# CANoPi.net
KiCad netlist of a schematic drawn in EAGLE
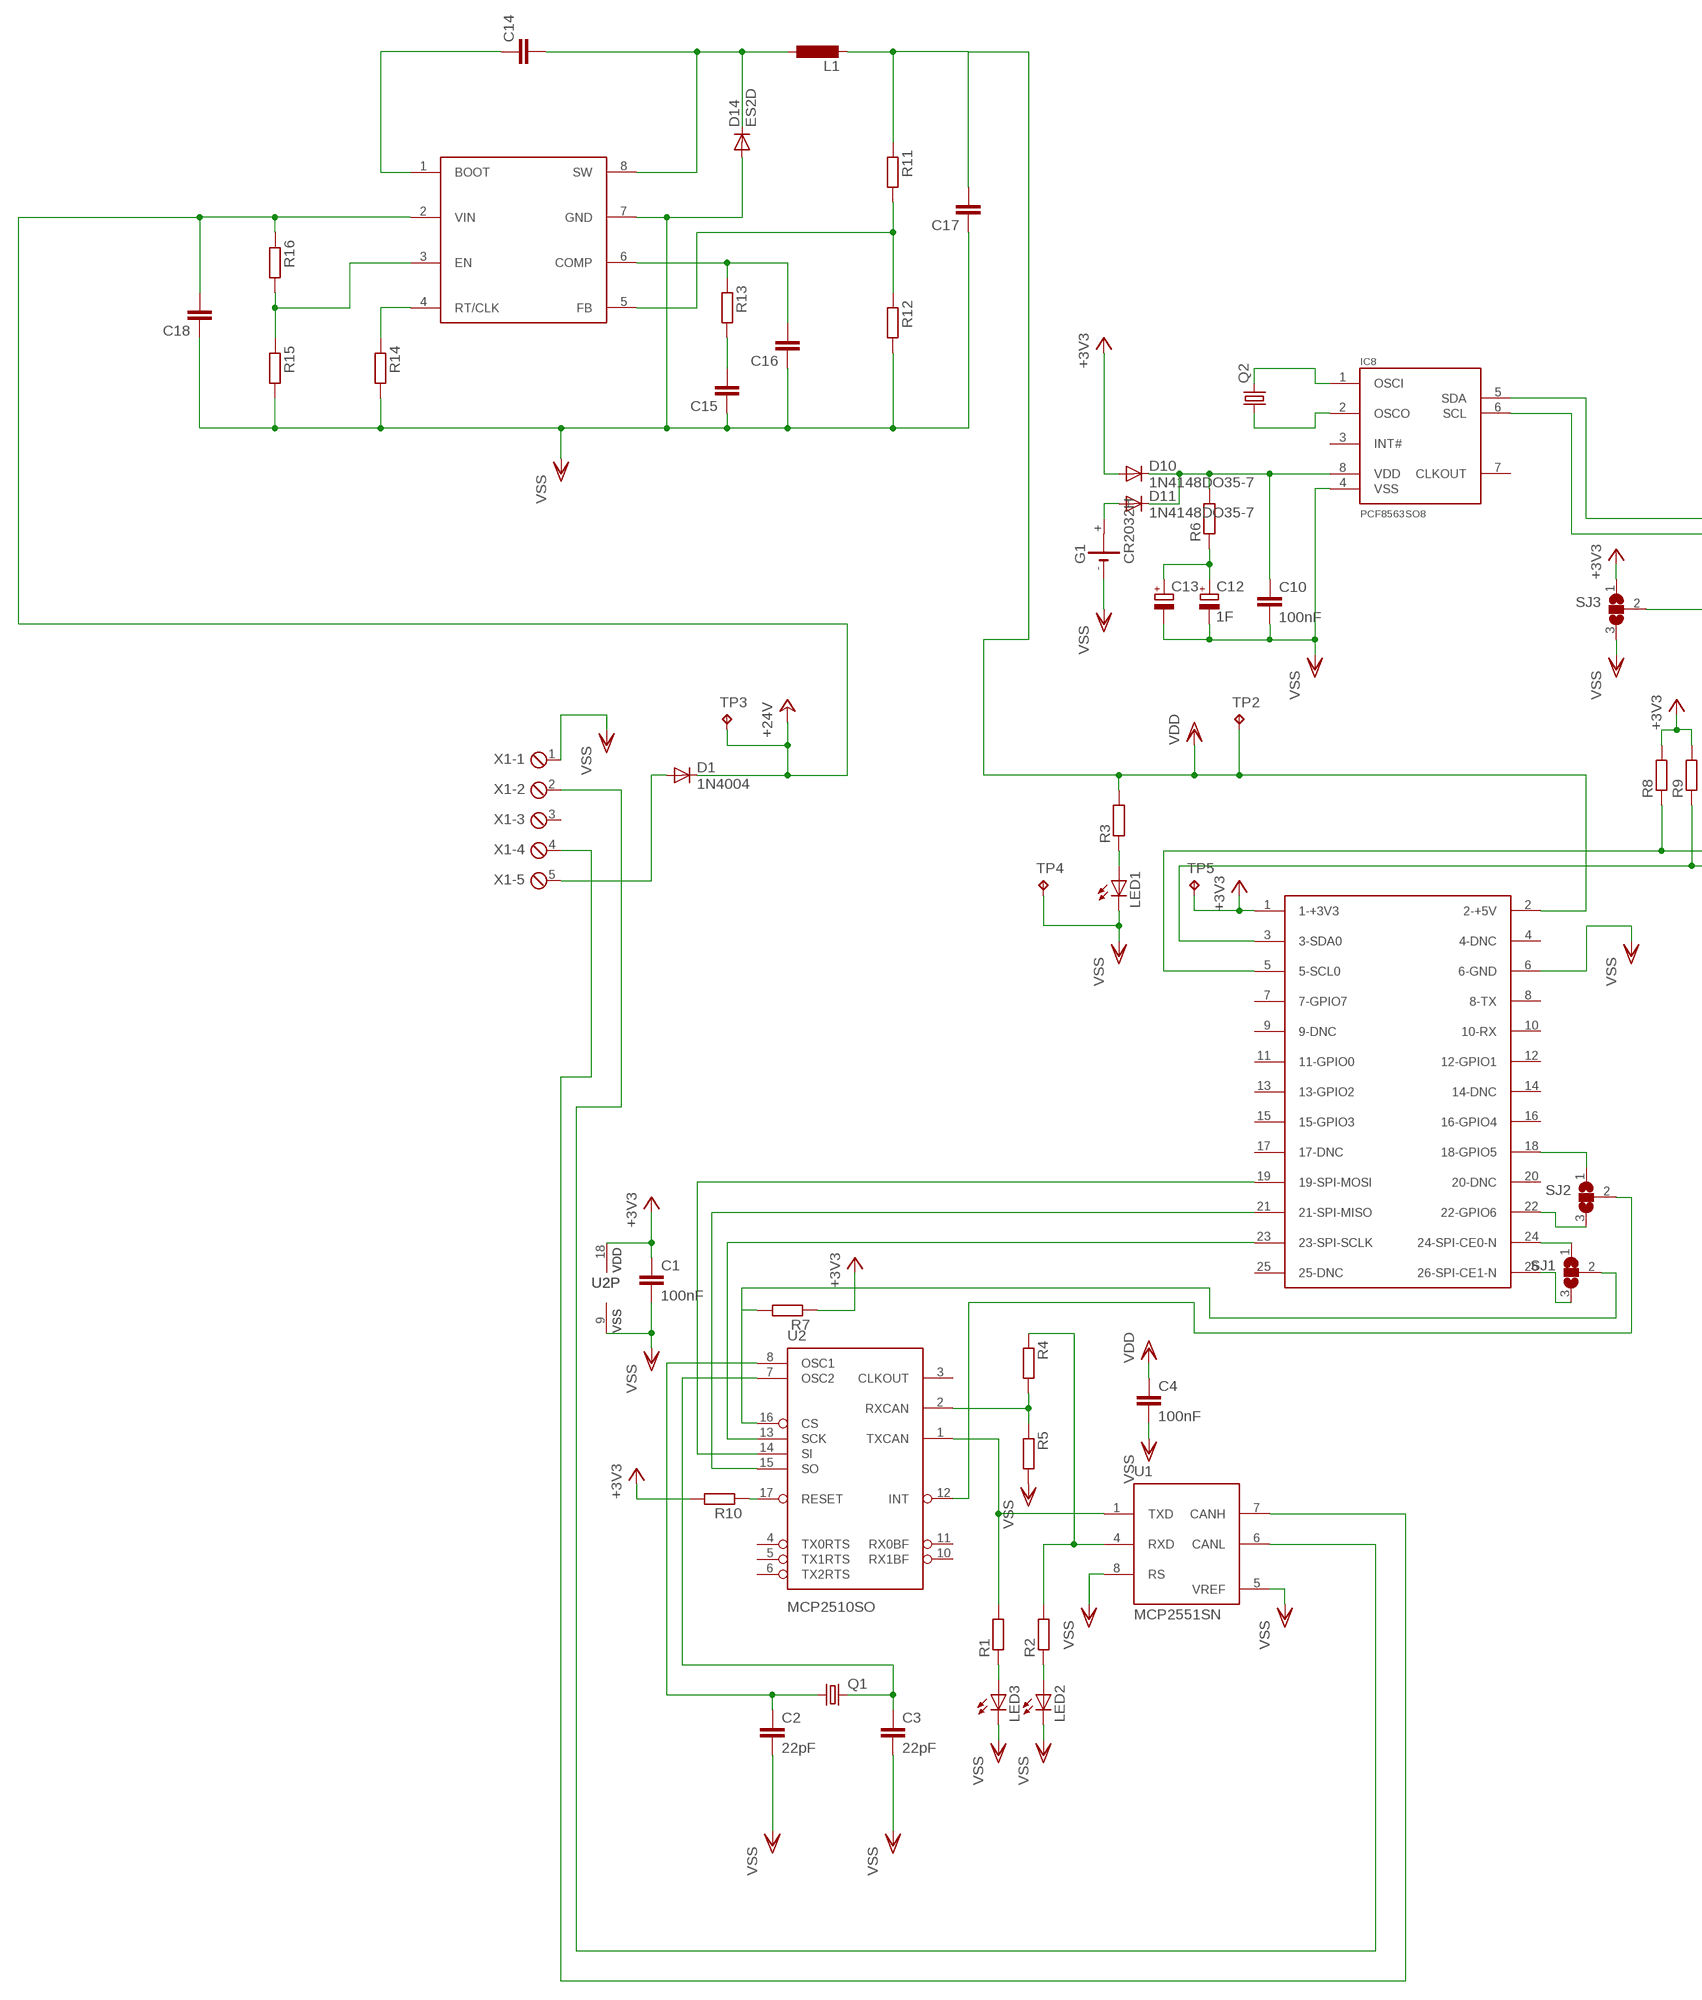
[diagram p0: schematic, sheet 1, part 1 of 2]
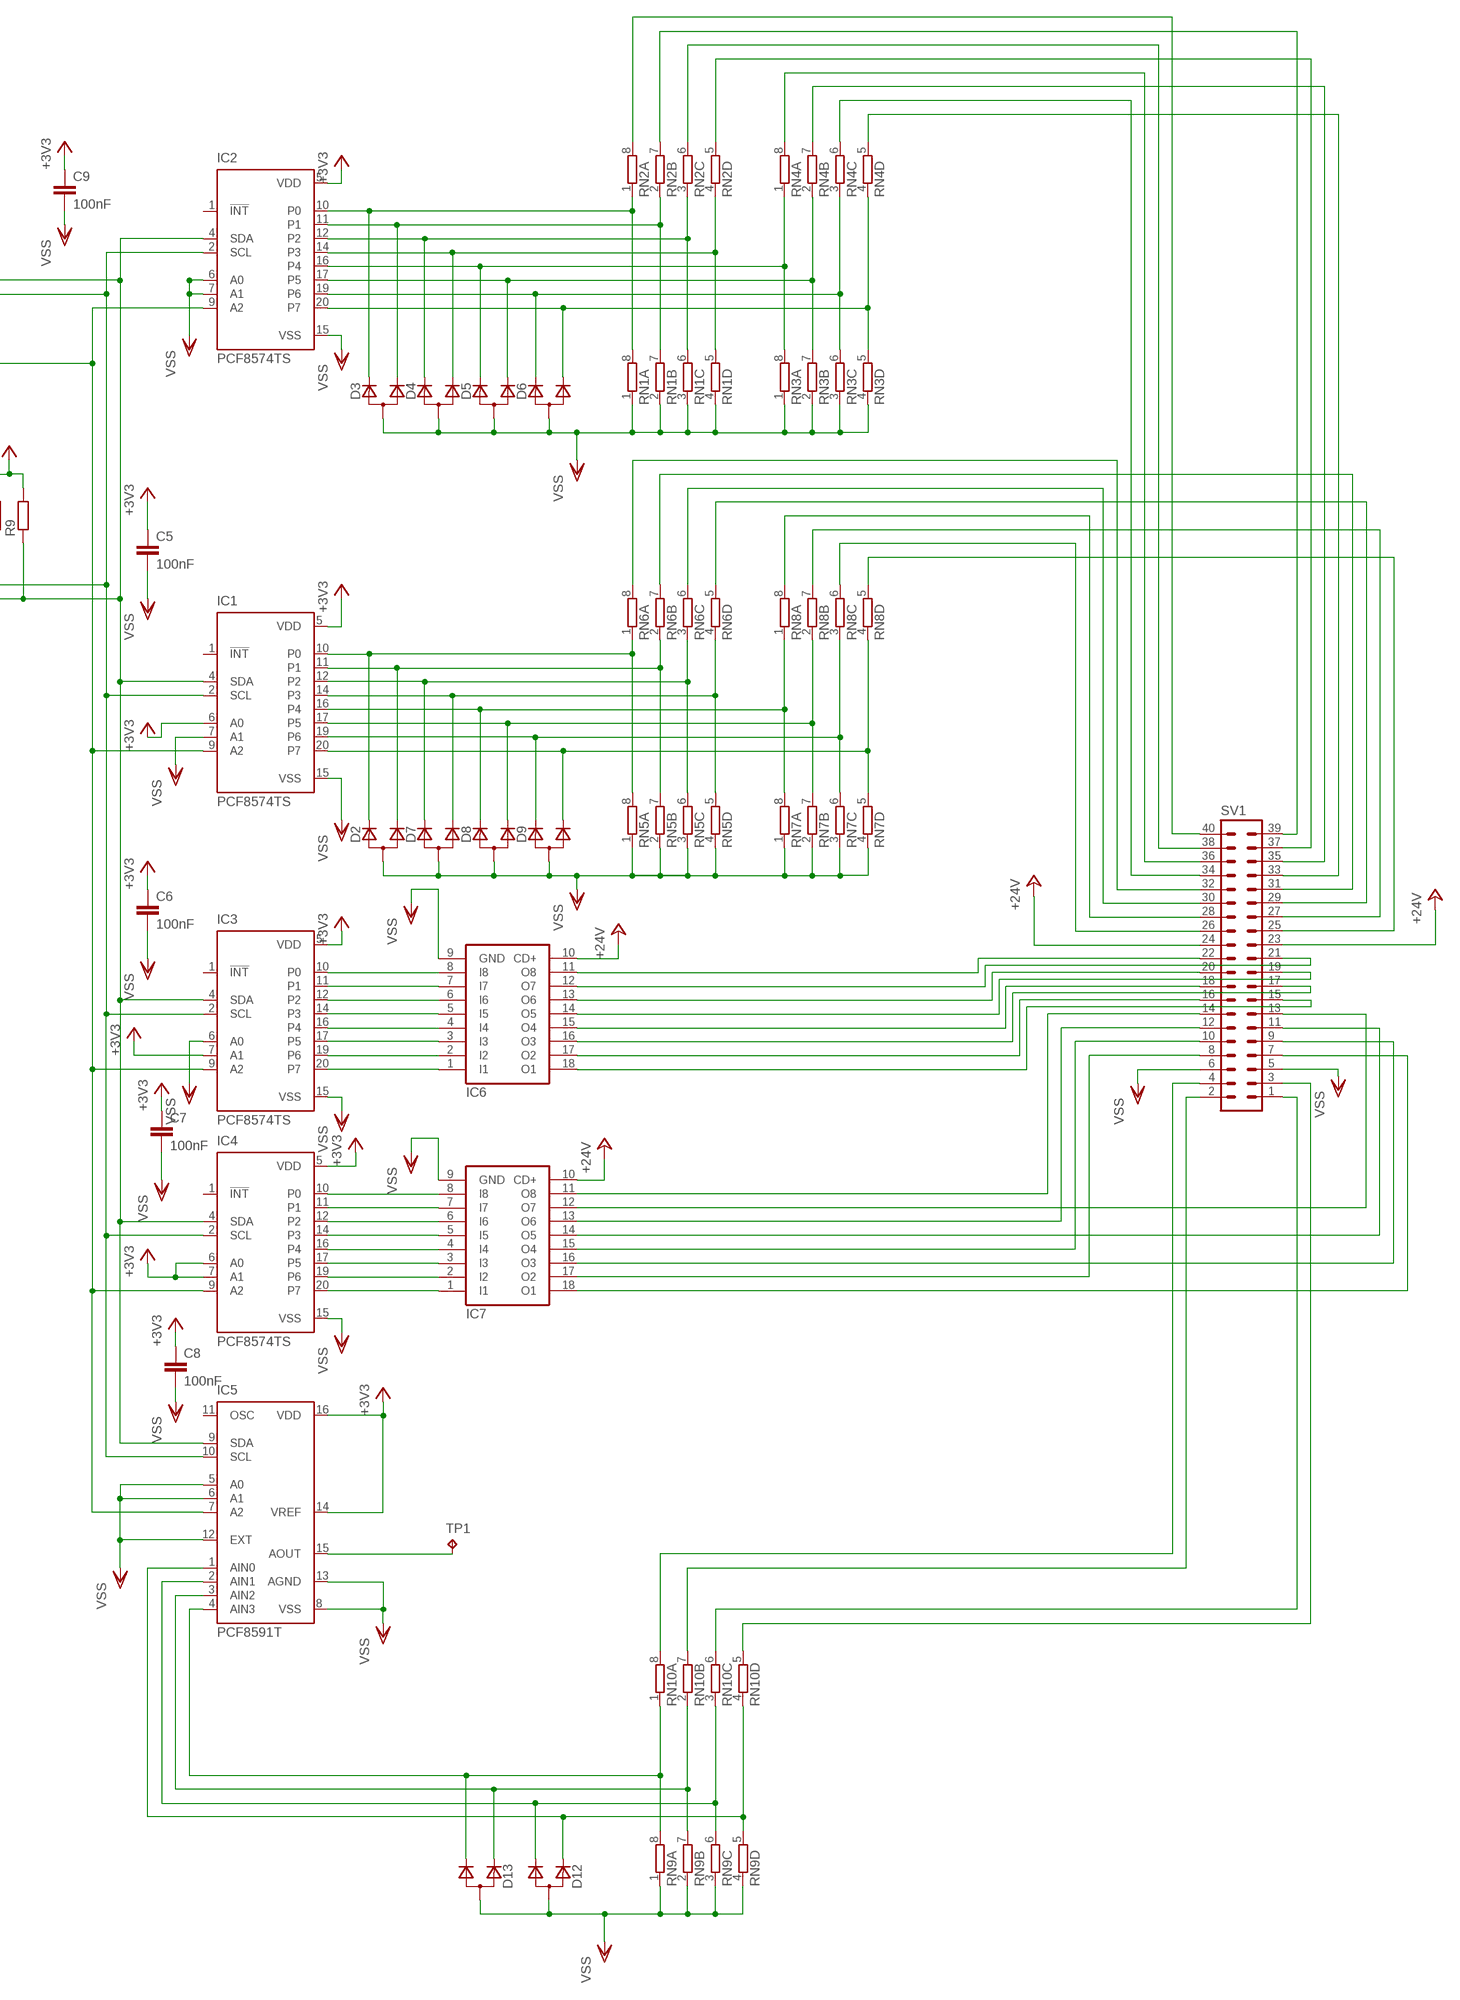
[diagram p1: schematic, sheet 1, part 2 of 2]

(export (version "E")
  (design (tool "Eeschema 10.0.6"))
  (components
    (comp (ref "C1")
      (value "100nF")
      (footprint "eagle-import:C0603")
      (libsource (lib "eagle-import") (part "C-EUC0603"))
    )
    (comp (ref "C2")
      (value "22pF")
      (footprint "eagle-import:C1206")
      (libsource (lib "eagle-import") (part "C-EUC1206"))
    )
    (comp (ref "C3")
      (value "22pF")
      (footprint "eagle-import:C1206")
      (libsource (lib "eagle-import") (part "C-EUC1206"))
    )
    (comp (ref "C4")
      (value "100nF")
      (footprint "eagle-import:C0603")
      (libsource (lib "eagle-import") (part "C-EUC0603"))
    )
    (comp (ref "C5")
      (value "100nF")
      (footprint "eagle-import:C0603")
      (libsource (lib "eagle-import") (part "C-EUC0603"))
    )
    (comp (ref "C6")
      (value "100nF")
      (footprint "eagle-import:C0603")
      (libsource (lib "eagle-import") (part "C-EUC0603"))
    )
    (comp (ref "C7")
      (value "100nF")
      (footprint "eagle-import:C0603")
      (libsource (lib "eagle-import") (part "C-EUC0603"))
    )
    (comp (ref "C8")
      (value "100nF")
      (footprint "eagle-import:C0603")
      (libsource (lib "eagle-import") (part "C-EUC0603"))
    )
    (comp (ref "C9")
      (value "100nF")
      (footprint "eagle-import:C0603")
      (libsource (lib "eagle-import") (part "C-EUC0603"))
    )
    (comp (ref "C10")
      (value "100nF")
      (footprint "eagle-import:C0603")
      (libsource (lib "eagle-import") (part "C-EUC0603"))
    )
    (comp (ref "C12")
      (value "1F")
      (footprint "eagle-import:CT3216")
      (libsource (lib "eagle-import") (part "CPOL-EUCT3216"))
    )
    (comp (ref "C13")
      (value "CPOL-EUE5-6")
      (footprint "eagle-import:E5-6")
      (libsource (lib "eagle-import") (part "CPOL-EUE5-6"))
    )
    (comp (ref "C14")
      (value "C-EUC0805")
      (footprint "eagle-import:C0805")
      (libsource (lib "eagle-import") (part "C-EUC0805"))
    )
    (comp (ref "C15")
      (value "C-EUC0805")
      (footprint "eagle-import:C0805")
      (libsource (lib "eagle-import") (part "C-EUC0805"))
    )
    (comp (ref "C16")
      (value "C-EUC0805")
      (footprint "eagle-import:C0805")
      (libsource (lib "eagle-import") (part "C-EUC0805"))
    )
    (comp (ref "C17")
      (value "C-EUC1210")
      (footprint "eagle-import:C1210")
      (libsource (lib "eagle-import") (part "C-EUC1210"))
    )
    (comp (ref "C18")
      (value "C-EUC1210")
      (footprint "eagle-import:C1210")
      (libsource (lib "eagle-import") (part "C-EUC1210"))
    )
    (comp (ref "D1")
      (value "1N4004")
      (footprint "eagle-import:DO41-10")
      (libsource (lib "eagle-import") (part "1N4004"))
    )
    (comp (ref "D2")
      (value "D_2CSOT23")
      (footprint "eagle-import:SOT-23")
      (libsource (lib "eagle-import") (part "D_2CSOT23"))
    )
    (comp (ref "D3")
      (value "D_2CSOT23")
      (footprint "eagle-import:SOT-23")
      (libsource (lib "eagle-import") (part "D_2CSOT23"))
    )
    (comp (ref "D4")
      (value "D_2CSOT23")
      (footprint "eagle-import:SOT-23")
      (libsource (lib "eagle-import") (part "D_2CSOT23"))
    )
    (comp (ref "D5")
      (value "D_2CSOT23")
      (footprint "eagle-import:SOT-23")
      (libsource (lib "eagle-import") (part "D_2CSOT23"))
    )
    (comp (ref "D6")
      (value "D_2CSOT23")
      (footprint "eagle-import:SOT-23")
      (libsource (lib "eagle-import") (part "D_2CSOT23"))
    )
    (comp (ref "D7")
      (value "D_2CSOT23")
      (footprint "eagle-import:SOT-23")
      (libsource (lib "eagle-import") (part "D_2CSOT23"))
    )
    (comp (ref "D8")
      (value "D_2CSOT23")
      (footprint "eagle-import:SOT-23")
      (libsource (lib "eagle-import") (part "D_2CSOT23"))
    )
    (comp (ref "D9")
      (value "D_2CSOT23")
      (footprint "eagle-import:SOT-23")
      (libsource (lib "eagle-import") (part "D_2CSOT23"))
    )
    (comp (ref "D10")
      (value "1N4148DO35-7")
      (footprint "eagle-import:DO35-7")
      (libsource (lib "eagle-import") (part "1N4148DO35-7"))
    )
    (comp (ref "D11")
      (value "1N4148DO35-7")
      (footprint "eagle-import:DO35-7")
      (libsource (lib "eagle-import") (part "1N4148DO35-7"))
    )
    (comp (ref "D12")
      (value "D_2CSOT23")
      (footprint "eagle-import:SOT-23")
      (fields (field (name "OC_FARNELL") "unknown") (field (name "OC_NEWARK") "unknown"))
      (libsource (lib "eagle-import") (part "D_2CSOT23"))
    )
    (comp (ref "D13")
      (value "D_2CSOT23")
      (footprint "eagle-import:SOT-23")
      (fields (field (name "OC_FARNELL") "unknown") (field (name "OC_NEWARK") "unknown"))
      (libsource (lib "eagle-import") (part "D_2CSOT23"))
    )
    (comp (ref "D14")
      (value "ES2D")
      (footprint "eagle-import:SMB")
      (libsource (lib "eagle-import") (part "ES2D"))
    )
    (comp (ref "G1")
      (value "CR2032H")
      (footprint "eagle-import:CR2032H")
      (libsource (lib "eagle-import") (part "CR2032H"))
    )
    (comp (ref "IC1")
      (value "PCF8574TS")
      (footprint "eagle-import:SSOP20")
      (fields (field (name "MPN") "PCF8574TS/3,118"))
      (libsource (lib "eagle-import") (part "PCF8574TS"))
    )
    (comp (ref "IC2")
      (value "PCF8574TS")
      (footprint "eagle-import:SSOP20")
      (fields (field (name "MPN") "PCF8574TS/3,118"))
      (libsource (lib "eagle-import") (part "PCF8574TS"))
    )
    (comp (ref "IC3")
      (value "PCF8574TS")
      (footprint "eagle-import:SSOP20")
      (fields (field (name "MPN") "PCF8574TS/3,118"))
      (libsource (lib "eagle-import") (part "PCF8574TS"))
    )
    (comp (ref "IC4")
      (value "PCF8574TS")
      (footprint "eagle-import:SSOP20")
      (fields (field (name "MPN") "PCF8574TS/3,118"))
      (libsource (lib "eagle-import") (part "PCF8574TS"))
    )
    (comp (ref "IC5")
      (value "PCF8591T")
      (footprint "eagle-import:SO16W")
      (fields (field (name "MPN") "PCF8591T/2,512"))
      (libsource (lib "eagle-import") (part "PCF8591T"))
    )
    (comp (ref "IC6")
      (value "ULN2804ASO18W")
      (footprint "eagle-import:SO18W")
      (libsource (lib "eagle-import") (part "ULN2804ASO18W"))
    )
    (comp (ref "IC7")
      (value "ULN2804ASO18W")
      (footprint "eagle-import:SO18W")
      (libsource (lib "eagle-import") (part "ULN2804ASO18W"))
    )
    (comp (ref "IC8")
      (value "PCF8563SO8")
      (footprint "eagle-import:SOIC8")
      (libsource (lib "eagle-import") (part "PCF8563SO8"))
    )
    (comp (ref "L1")
      (value "L-EUWE-TPC")
      (footprint "eagle-import:POWER-CHOKE_WE-TPC")
      (libsource (lib "eagle-import") (part "L-EUWE-TPC"))
    )
    (comp (ref "LED1")
      (value "LEDCHIPLED_1206")
      (footprint "eagle-import:CHIPLED_1206")
      (libsource (lib "eagle-import") (part "LEDCHIPLED_1206"))
    )
    (comp (ref "LED2")
      (value "LEDCHIPLED_1206")
      (footprint "eagle-import:CHIPLED_1206")
      (libsource (lib "eagle-import") (part "LEDCHIPLED_1206"))
    )
    (comp (ref "LED3")
      (value "LEDCHIPLED_1206")
      (footprint "eagle-import:CHIPLED_1206")
      (libsource (lib "eagle-import") (part "LEDCHIPLED_1206"))
    )
    (comp (ref "Q1")
      (value "CRYSTALHC49S")
      (footprint "eagle-import:HC49_S")
      (libsource (lib "eagle-import") (part "CRYSTALHC49S"))
    )
    (comp (ref "Q2")
      (value "CRYSTALHC49S")
      (footprint "eagle-import:HC49_S")
      (fields (field (name "OC_FARNELL") "1667008") (field (name "OC_NEWARK") "unknown"))
      (libsource (lib "eagle-import") (part "CRYSTALHC49S"))
    )
    (comp (ref "R1")
      (value "R-EU_R0805")
      (footprint "eagle-import:R0805")
      (libsource (lib "eagle-import") (part "R-EU_R0805"))
    )
    (comp (ref "R2")
      (value "R-EU_R0805")
      (footprint "eagle-import:R0805")
      (libsource (lib "eagle-import") (part "R-EU_R0805"))
    )
    (comp (ref "R3")
      (value "R-EU_R0805")
      (footprint "eagle-import:R0805")
      (libsource (lib "eagle-import") (part "R-EU_R0805"))
    )
    (comp (ref "R4")
      (value "R-EU_R0805")
      (footprint "eagle-import:R0805")
      (libsource (lib "eagle-import") (part "R-EU_R0805"))
    )
    (comp (ref "R5")
      (value "R-EU_R0805")
      (footprint "eagle-import:R0805")
      (libsource (lib "eagle-import") (part "R-EU_R0805"))
    )
    (comp (ref "R6")
      (value "R-EU_R0805")
      (footprint "eagle-import:R0805")
      (libsource (lib "eagle-import") (part "R-EU_R0805"))
    )
    (comp (ref "R7")
      (value "R-EU_R0805")
      (footprint "eagle-import:R0805")
      (libsource (lib "eagle-import") (part "R-EU_R0805"))
    )
    (comp (ref "R8")
      (value "R-EU_R0805")
      (footprint "eagle-import:R0805")
      (libsource (lib "eagle-import") (part "R-EU_R0805"))
    )
    (comp (ref "R9")
      (value "R-EU_R0805")
      (footprint "eagle-import:R0805")
      (libsource (lib "eagle-import") (part "R-EU_R0805"))
    )
    (comp (ref "R10")
      (value "R-EU_R0805")
      (footprint "eagle-import:R0805")
      (libsource (lib "eagle-import") (part "R-EU_R0805"))
    )
    (comp (ref "R11")
      (value "R-EU_R0805")
      (footprint "eagle-import:R0805")
      (libsource (lib "eagle-import") (part "R-EU_R0805"))
    )
    (comp (ref "R12")
      (value "R-EU_R0805")
      (footprint "eagle-import:R0805")
      (libsource (lib "eagle-import") (part "R-EU_R0805"))
    )
    (comp (ref "R13")
      (value "R-EU_R0805")
      (footprint "eagle-import:R0805")
      (libsource (lib "eagle-import") (part "R-EU_R0805"))
    )
    (comp (ref "R14")
      (value "R-EU_R0805")
      (footprint "eagle-import:R0805")
      (libsource (lib "eagle-import") (part "R-EU_R0805"))
    )
    (comp (ref "R15")
      (value "R-EU_R0805")
      (footprint "eagle-import:R0805")
      (libsource (lib "eagle-import") (part "R-EU_R0805"))
    )
    (comp (ref "R16")
      (value "R-EU_R0805")
      (footprint "eagle-import:R0805")
      (libsource (lib "eagle-import") (part "R-EU_R0805"))
    )
    (comp (ref "RN1")
      (value "4R-NEXBS8V")
      (footprint "eagle-import:EXBS8V")
      (libsource (lib "eagle-import") (part "4R-NEXBS8V"))
    )
    (comp (ref "RN2")
      (value "4R-NEXBS8V")
      (footprint "eagle-import:EXBS8V")
      (libsource (lib "eagle-import") (part "4R-NEXBS8V"))
    )
    (comp (ref "RN3")
      (value "4R-NEXBS8V")
      (footprint "eagle-import:EXBS8V")
      (libsource (lib "eagle-import") (part "4R-NEXBS8V"))
    )
    (comp (ref "RN4")
      (value "4R-NEXBS8V")
      (footprint "eagle-import:EXBS8V")
      (libsource (lib "eagle-import") (part "4R-NEXBS8V"))
    )
    (comp (ref "RN5")
      (value "4R-NEXBS8V")
      (footprint "eagle-import:EXBS8V")
      (libsource (lib "eagle-import") (part "4R-NEXBS8V"))
    )
    (comp (ref "RN6")
      (value "4R-NEXBS8V")
      (footprint "eagle-import:EXBS8V")
      (libsource (lib "eagle-import") (part "4R-NEXBS8V"))
    )
    (comp (ref "RN7")
      (value "4R-NEXBS8V")
      (footprint "eagle-import:EXBS8V")
      (libsource (lib "eagle-import") (part "4R-NEXBS8V"))
    )
    (comp (ref "RN8")
      (value "4R-NEXBS8V")
      (footprint "eagle-import:EXBS8V")
      (libsource (lib "eagle-import") (part "4R-NEXBS8V"))
    )
    (comp (ref "RN9")
      (value "4R-NEXBS8V")
      (footprint "eagle-import:EXBS8V")
      (fields (field (name "OC_FARNELL") "unknown") (field (name "OC_NEWARK") "unknown"))
      (libsource (lib "eagle-import") (part "4R-NEXBS8V"))
    )
    (comp (ref "RN10")
      (value "4R-NEXBS8V")
      (footprint "eagle-import:EXBS8V")
      (fields (field (name "OC_FARNELL") "unknown") (field (name "OC_NEWARK") "unknown"))
      (libsource (lib "eagle-import") (part "4R-NEXBS8V"))
    )
    (comp (ref "SJ1")
      (value "SJ2W")
      (footprint "eagle-import:SJ_2")
      (libsource (lib "eagle-import") (part "SJ2W"))
    )
    (comp (ref "SJ2")
      (value "SJ2W")
      (footprint "eagle-import:SJ_2")
      (libsource (lib "eagle-import") (part "SJ2W"))
    )
    (comp (ref "SJ3")
      (value "SJ2W")
      (footprint "eagle-import:SJ_2")
      (libsource (lib "eagle-import") (part "SJ2W"))
    )
    (comp (ref "SV1")
      (value "ML40L")
      (footprint "eagle-import:ML40L")
      (libsource (lib "eagle-import") (part "ML40L"))
    )
    (comp (ref "TP1")
      (value "TPPAD1-13")
      (footprint "eagle-import:P1-13")
      (libsource (lib "eagle-import") (part "TPPAD1-13"))
    )
    (comp (ref "TP2")
      (value "TPPAD1-13")
      (footprint "eagle-import:P1-13")
      (libsource (lib "eagle-import") (part "TPPAD1-13"))
    )
    (comp (ref "TP3")
      (value "TPPAD1-13")
      (footprint "eagle-import:P1-13")
      (libsource (lib "eagle-import") (part "TPPAD1-13"))
    )
    (comp (ref "TP4")
      (value "TPPAD1-13")
      (footprint "eagle-import:P1-13")
      (libsource (lib "eagle-import") (part "TPPAD1-13"))
    )
    (comp (ref "TP5")
      (value "TPPAD1-13")
      (footprint "eagle-import:P1-13")
      (libsource (lib "eagle-import") (part "TPPAD1-13"))
    )
    (comp (ref "U$1")
      (value "RASPBERRY-PI")
      (footprint "eagle-import:RASPBERRY-PI")
      (libsource (lib "eagle-import") (part "RASPBERRY-PI"))
    )
    (comp (ref "U$2")
      (value "TPS54340")
      (footprint "eagle-import:SO-08")
      (libsource (lib "eagle-import") (part "TPS54340"))
    )
    (comp (ref "U1")
      (value "MCP2551SN")
      (footprint "eagle-import:SO-08")
      (libsource (lib "eagle-import") (part "MCP2551SN"))
    )
    (comp (ref "U2")
      (value "MCP2510SO")
      (footprint "eagle-import:SO-18W")
      (libsource (lib "eagle-import") (part "MCP2510SO"))
    )
    (comp (ref "X1")
      (value "MPT5")
      (footprint "eagle-import:5POL254")
      (libsource (lib "eagle-import") (part "MPT5"))
    )
  )
  (nets
    (net (code "1") (name "+3V3") (class "Default")
      (node (ref "C1") (pin "1") (pinfunction "1_1") (pintype "passive"))
      (node (ref "C5") (pin "1") (pinfunction "1_1") (pintype "passive"))
      (node (ref "C6") (pin "1") (pinfunction "1_1") (pintype "passive"))
      (node (ref "C7") (pin "1") (pinfunction "1_1") (pintype "passive"))
      (node (ref "C8") (pin "1") (pinfunction "1_1") (pintype "passive"))
      (node (ref "C9") (pin "1") (pinfunction "1_1") (pintype "passive"))
      (node (ref "D10") (pin "A") (pinfunction "A_A") (pintype "passive"))
      (node (ref "IC1") (pin "5") (pinfunction "VDD_5") (pintype "power_in"))
      (node (ref "IC1") (pin "6") (pinfunction "A0_6") (pintype "input"))
      (node (ref "IC2") (pin "5") (pinfunction "VDD_5") (pintype "power_in"))
      (node (ref "IC3") (pin "5") (pinfunction "VDD_5") (pintype "power_in"))
      (node (ref "IC3") (pin "7") (pinfunction "A1_7") (pintype "input"))
      (node (ref "IC4") (pin "5") (pinfunction "VDD_5") (pintype "power_in"))
      (node (ref "IC4") (pin "6") (pinfunction "A0_6") (pintype "input"))
      (node (ref "IC4") (pin "7") (pinfunction "A1_7") (pintype "input"))
      (node (ref "IC5") (pin "14") (pinfunction "VREF_14") (pintype "input"))
      (node (ref "IC5") (pin "16") (pinfunction "VDD_16") (pintype "power_in"))
      (node (ref "R10") (pin "2") (pinfunction "2_2") (pintype "passive"))
      (node (ref "R7") (pin "1") (pinfunction "1_1") (pintype "passive"))
      (node (ref "R8") (pin "2") (pinfunction "2_2") (pintype "passive"))
      (node (ref "R9") (pin "2") (pinfunction "2_2") (pintype "passive"))
      (node (ref "SJ3") (pin "1") (pinfunction "1_1") (pintype "passive"))
      (node (ref "TP5") (pin "TP") (pinfunction "TP_TP") (pintype "input"))
      (node (ref "U$1") (pin "1") (pinfunction "1-+3V3_1") (pintype "bidirectional"))
      (node (ref "U2") (pin "18") (pinfunction "VDD_18") (pintype "power_in"))
    )
    (net (code "2") (name "+24V") (class "Default")
      (node (ref "C18") (pin "2") (pinfunction "2_2") (pintype "passive"))
      (node (ref "D1") (pin "C") (pinfunction "C_C") (pintype "passive"))
      (node (ref "IC6") (pin "10") (pinfunction "CD+_10") (pintype "passive"))
      (node (ref "IC7") (pin "10") (pinfunction "CD+_10") (pintype "passive"))
      (node (ref "R16") (pin "1") (pinfunction "1_1") (pintype "passive"))
      (node (ref "SV1") (pin "23") (pinfunction "23_23") (pintype "passive"))
      (node (ref "SV1") (pin "24") (pinfunction "24_24") (pintype "passive"))
      (node (ref "TP3") (pin "TP") (pinfunction "TP_TP") (pintype "input"))
      (node (ref "U$2") (pin "2") (pinfunction "VIN_2") (pintype "bidirectional"))
    )
    (net (code "3") (name "Net-(C12-Pad+)") (class "Default")
      (node (ref "C12") (pin "+") (pinfunction "+_+") (pintype "passive"))
      (node (ref "C13") (pin "+") (pinfunction "+_+") (pintype "passive"))
      (node (ref "R6") (pin "1") (pinfunction "1_1") (pintype "passive"))
    )
    (net (code "4") (name "Net-(C15-Pad2)") (class "Default")
      (node (ref "C15") (pin "2") (pinfunction "2_2") (pintype "passive"))
      (node (ref "R13") (pin "2") (pinfunction "2_2") (pintype "passive"))
    )
    (net (code "5") (name "Net-(D2-C1)") (class "Default")
      (node (ref "D2") (pin "2") (pinfunction "C1_2") (pintype "passive"))
      (node (ref "IC1") (pin "10") (pinfunction "P0_10") (pintype "bidirectional"))
      (node (ref "RN5") (pin "8") (pinfunction "2_8") (pintype "passive"))
      (node (ref "RN6") (pin "1") (pinfunction "1_1") (pintype "passive"))
    )
    (net (code "6") (name "Net-(D2-C2)") (class "Default")
      (node (ref "D2") (pin "3") (pinfunction "C2_3") (pintype "passive"))
      (node (ref "IC1") (pin "11") (pinfunction "P1_11") (pintype "bidirectional"))
      (node (ref "RN5") (pin "7") (pinfunction "2_7") (pintype "passive"))
      (node (ref "RN6") (pin "2") (pinfunction "1_2") (pintype "passive"))
    )
    (net (code "7") (name "Net-(D3-C1)") (class "Default")
      (node (ref "D3") (pin "2") (pinfunction "C1_2") (pintype "passive"))
      (node (ref "IC2") (pin "10") (pinfunction "P0_10") (pintype "bidirectional"))
      (node (ref "RN1") (pin "8") (pinfunction "2_8") (pintype "passive"))
      (node (ref "RN2") (pin "1") (pinfunction "1_1") (pintype "passive"))
    )
    (net (code "8") (name "Net-(D3-C2)") (class "Default")
      (node (ref "D3") (pin "3") (pinfunction "C2_3") (pintype "passive"))
      (node (ref "IC2") (pin "11") (pinfunction "P1_11") (pintype "bidirectional"))
      (node (ref "RN1") (pin "7") (pinfunction "2_7") (pintype "passive"))
      (node (ref "RN2") (pin "2") (pinfunction "1_2") (pintype "passive"))
    )
    (net (code "9") (name "Net-(D4-C1)") (class "Default")
      (node (ref "D4") (pin "2") (pinfunction "C1_2") (pintype "passive"))
      (node (ref "IC2") (pin "12") (pinfunction "P2_12") (pintype "bidirectional"))
      (node (ref "RN1") (pin "6") (pinfunction "2_6") (pintype "passive"))
      (node (ref "RN2") (pin "3") (pinfunction "1_3") (pintype "passive"))
    )
    (net (code "10") (name "Net-(D4-C2)") (class "Default")
      (node (ref "D4") (pin "3") (pinfunction "C2_3") (pintype "passive"))
      (node (ref "IC2") (pin "14") (pinfunction "P3_14") (pintype "bidirectional"))
      (node (ref "RN1") (pin "5") (pinfunction "2_5") (pintype "passive"))
      (node (ref "RN2") (pin "4") (pinfunction "1_4") (pintype "passive"))
    )
    (net (code "11") (name "Net-(D5-C1)") (class "Default")
      (node (ref "D5") (pin "2") (pinfunction "C1_2") (pintype "passive"))
      (node (ref "IC2") (pin "16") (pinfunction "P4_16") (pintype "bidirectional"))
      (node (ref "RN3") (pin "8") (pinfunction "2_8") (pintype "passive"))
      (node (ref "RN4") (pin "1") (pinfunction "1_1") (pintype "passive"))
    )
    (net (code "12") (name "Net-(D5-C2)") (class "Default")
      (node (ref "D5") (pin "3") (pinfunction "C2_3") (pintype "passive"))
      (node (ref "IC2") (pin "17") (pinfunction "P5_17") (pintype "bidirectional"))
      (node (ref "RN3") (pin "7") (pinfunction "2_7") (pintype "passive"))
      (node (ref "RN4") (pin "2") (pinfunction "1_2") (pintype "passive"))
    )
    (net (code "13") (name "Net-(D6-C1)") (class "Default")
      (node (ref "D6") (pin "2") (pinfunction "C1_2") (pintype "passive"))
      (node (ref "IC2") (pin "19") (pinfunction "P6_19") (pintype "bidirectional"))
      (node (ref "RN3") (pin "6") (pinfunction "2_6") (pintype "passive"))
      (node (ref "RN4") (pin "3") (pinfunction "1_3") (pintype "passive"))
    )
    (net (code "14") (name "Net-(D6-C2)") (class "Default")
      (node (ref "D6") (pin "3") (pinfunction "C2_3") (pintype "passive"))
      (node (ref "IC2") (pin "20") (pinfunction "P7_20") (pintype "bidirectional"))
      (node (ref "RN3") (pin "5") (pinfunction "2_5") (pintype "passive"))
      (node (ref "RN4") (pin "4") (pinfunction "1_4") (pintype "passive"))
    )
    (net (code "15") (name "Net-(D7-C1)") (class "Default")
      (node (ref "D7") (pin "2") (pinfunction "C1_2") (pintype "passive"))
      (node (ref "IC1") (pin "12") (pinfunction "P2_12") (pintype "bidirectional"))
      (node (ref "RN5") (pin "6") (pinfunction "2_6") (pintype "passive"))
      (node (ref "RN6") (pin "3") (pinfunction "1_3") (pintype "passive"))
    )
    (net (code "16") (name "Net-(D7-C2)") (class "Default")
      (node (ref "D7") (pin "3") (pinfunction "C2_3") (pintype "passive"))
      (node (ref "IC1") (pin "14") (pinfunction "P3_14") (pintype "bidirectional"))
      (node (ref "RN5") (pin "5") (pinfunction "2_5") (pintype "passive"))
      (node (ref "RN6") (pin "4") (pinfunction "1_4") (pintype "passive"))
    )
    (net (code "17") (name "Net-(D8-C1)") (class "Default")
      (node (ref "D8") (pin "2") (pinfunction "C1_2") (pintype "passive"))
      (node (ref "IC1") (pin "16") (pinfunction "P4_16") (pintype "bidirectional"))
      (node (ref "RN7") (pin "8") (pinfunction "2_8") (pintype "passive"))
      (node (ref "RN8") (pin "1") (pinfunction "1_1") (pintype "passive"))
    )
    (net (code "18") (name "Net-(D8-C2)") (class "Default")
      (node (ref "D8") (pin "3") (pinfunction "C2_3") (pintype "passive"))
      (node (ref "IC1") (pin "17") (pinfunction "P5_17") (pintype "bidirectional"))
      (node (ref "RN7") (pin "7") (pinfunction "2_7") (pintype "passive"))
      (node (ref "RN8") (pin "2") (pinfunction "1_2") (pintype "passive"))
    )
    (net (code "19") (name "Net-(D9-C1)") (class "Default")
      (node (ref "D9") (pin "2") (pinfunction "C1_2") (pintype "passive"))
      (node (ref "IC1") (pin "19") (pinfunction "P6_19") (pintype "bidirectional"))
      (node (ref "RN7") (pin "6") (pinfunction "2_6") (pintype "passive"))
      (node (ref "RN8") (pin "3") (pinfunction "1_3") (pintype "passive"))
    )
    (net (code "20") (name "Net-(D9-C2)") (class "Default")
      (node (ref "D9") (pin "3") (pinfunction "C2_3") (pintype "passive"))
      (node (ref "IC1") (pin "20") (pinfunction "P7_20") (pintype "bidirectional"))
      (node (ref "RN7") (pin "5") (pinfunction "2_5") (pintype "passive"))
      (node (ref "RN8") (pin "4") (pinfunction "1_4") (pintype "passive"))
    )
    (net (code "21") (name "Net-(D11-PadA)") (class "Default")
      (node (ref "D11") (pin "A") (pinfunction "A_A") (pintype "passive"))
      (node (ref "G1") (pin "+") (pinfunction "+_+") (pintype "passive"))
    )
    (net (code "22") (name "Net-(D12-C1)") (class "Default")
      (node (ref "D12") (pin "2") (pinfunction "C1_2") (pintype "passive"))
      (node (ref "IC5") (pin "1") (pinfunction "AIN0_1") (pintype "input"))
      (node (ref "RN10") (pin "4") (pinfunction "1_4") (pintype "passive"))
      (node (ref "RN9") (pin "5") (pinfunction "2_5") (pintype "passive"))
    )
    (net (code "23") (name "Net-(D12-C2)") (class "Default")
      (node (ref "D12") (pin "3") (pinfunction "C2_3") (pintype "passive"))
      (node (ref "IC5") (pin "2") (pinfunction "AIN1_2") (pintype "input"))
      (node (ref "RN10") (pin "3") (pinfunction "1_3") (pintype "passive"))
      (node (ref "RN9") (pin "6") (pinfunction "2_6") (pintype "passive"))
    )
    (net (code "24") (name "Net-(D13-C1)") (class "Default")
      (node (ref "D13") (pin "2") (pinfunction "C1_2") (pintype "passive"))
      (node (ref "IC5") (pin "3") (pinfunction "AIN2_3") (pintype "input"))
      (node (ref "RN10") (pin "2") (pinfunction "1_2") (pintype "passive"))
      (node (ref "RN9") (pin "7") (pinfunction "2_7") (pintype "passive"))
    )
    (net (code "25") (name "Net-(D13-C2)") (class "Default")
      (node (ref "D13") (pin "3") (pinfunction "C2_3") (pintype "passive"))
      (node (ref "IC5") (pin "4") (pinfunction "AIN3_4") (pintype "input"))
      (node (ref "RN10") (pin "1") (pinfunction "1_1") (pintype "passive"))
      (node (ref "RN9") (pin "8") (pinfunction "2_8") (pintype "passive"))
    )
    (net (code "26") (name "Net-(IC1-A2)") (class "Default")
      (node (ref "IC1") (pin "9") (pinfunction "A2_9") (pintype "input"))
      (node (ref "IC2") (pin "9") (pinfunction "A2_9") (pintype "input"))
      (node (ref "IC3") (pin "9") (pinfunction "A2_9") (pintype "input"))
      (node (ref "IC4") (pin "9") (pinfunction "A2_9") (pintype "input"))
      (node (ref "IC5") (pin "7") (pinfunction "A2_7") (pintype "input"))
      (node (ref "SJ3") (pin "2") (pinfunction "2_2") (pintype "passive"))
    )
    (net (code "27") (name "Net-(IC1-SCL)") (class "Default")
      (node (ref "IC1") (pin "2") (pinfunction "SCL_2") (pintype "input"))
      (node (ref "IC2") (pin "2") (pinfunction "SCL_2") (pintype "input"))
      (node (ref "IC3") (pin "2") (pinfunction "SCL_2") (pintype "input"))
      (node (ref "IC4") (pin "2") (pinfunction "SCL_2") (pintype "input"))
      (node (ref "IC5") (pin "10") (pinfunction "SCL_10") (pintype "input"))
      (node (ref "IC8") (pin "6") (pinfunction "SCL_6") (pintype "bidirectional"))
      (node (ref "R8") (pin "1") (pinfunction "1_1") (pintype "passive"))
      (node (ref "U$1") (pin "5") (pinfunction "5-SCL0_5") (pintype "bidirectional"))
    )
    (net (code "28") (name "Net-(IC1-SDA)") (class "Default")
      (node (ref "IC1") (pin "4") (pinfunction "SDA_4") (pintype "bidirectional"))
      (node (ref "IC2") (pin "4") (pinfunction "SDA_4") (pintype "bidirectional"))
      (node (ref "IC3") (pin "4") (pinfunction "SDA_4") (pintype "bidirectional"))
      (node (ref "IC4") (pin "4") (pinfunction "SDA_4") (pintype "bidirectional"))
      (node (ref "IC5") (pin "9") (pinfunction "SDA_9") (pintype "bidirectional"))
      (node (ref "IC8") (pin "5") (pinfunction "SDA_5") (pintype "bidirectional"))
      (node (ref "R9") (pin "1") (pinfunction "1_1") (pintype "passive"))
      (node (ref "U$1") (pin "3") (pinfunction "3-SDA0_3") (pintype "bidirectional"))
    )
    (net (code "29") (name "Net-(IC3-P0)") (class "Default")
      (node (ref "IC3") (pin "10") (pinfunction "P0_10") (pintype "bidirectional"))
      (node (ref "IC6") (pin "8") (pinfunction "I8_8") (pintype "input"))
    )
    (net (code "30") (name "Net-(IC3-P1)") (class "Default")
      (node (ref "IC3") (pin "11") (pinfunction "P1_11") (pintype "bidirectional"))
      (node (ref "IC6") (pin "7") (pinfunction "I7_7") (pintype "input"))
    )
    (net (code "31") (name "Net-(IC3-P2)") (class "Default")
      (node (ref "IC3") (pin "12") (pinfunction "P2_12") (pintype "bidirectional"))
      (node (ref "IC6") (pin "6") (pinfunction "I6_6") (pintype "input"))
    )
    (net (code "32") (name "Net-(IC3-P3)") (class "Default")
      (node (ref "IC3") (pin "14") (pinfunction "P3_14") (pintype "bidirectional"))
      (node (ref "IC6") (pin "5") (pinfunction "I5_5") (pintype "input"))
    )
    (net (code "33") (name "Net-(IC3-P4)") (class "Default")
      (node (ref "IC3") (pin "16") (pinfunction "P4_16") (pintype "bidirectional"))
      (node (ref "IC6") (pin "4") (pinfunction "I4_4") (pintype "input"))
    )
    (net (code "34") (name "Net-(IC3-P5)") (class "Default")
      (node (ref "IC3") (pin "17") (pinfunction "P5_17") (pintype "bidirectional"))
      (node (ref "IC6") (pin "3") (pinfunction "I3_3") (pintype "input"))
    )
    (net (code "35") (name "Net-(IC3-P6)") (class "Default")
      (node (ref "IC3") (pin "19") (pinfunction "P6_19") (pintype "bidirectional"))
      (node (ref "IC6") (pin "2") (pinfunction "I2_2") (pintype "input"))
    )
    (net (code "36") (name "Net-(IC3-P7)") (class "Default")
      (node (ref "IC3") (pin "20") (pinfunction "P7_20") (pintype "bidirectional"))
      (node (ref "IC6") (pin "1") (pinfunction "I1_1") (pintype "input"))
    )
    (net (code "37") (name "Net-(IC4-P0)") (class "Default")
      (node (ref "IC4") (pin "10") (pinfunction "P0_10") (pintype "bidirectional"))
      (node (ref "IC7") (pin "8") (pinfunction "I8_8") (pintype "input"))
    )
    (net (code "38") (name "Net-(IC4-P1)") (class "Default")
      (node (ref "IC4") (pin "11") (pinfunction "P1_11") (pintype "bidirectional"))
      (node (ref "IC7") (pin "7") (pinfunction "I7_7") (pintype "input"))
    )
    (net (code "39") (name "Net-(IC4-P2)") (class "Default")
      (node (ref "IC4") (pin "12") (pinfunction "P2_12") (pintype "bidirectional"))
      (node (ref "IC7") (pin "6") (pinfunction "I6_6") (pintype "input"))
    )
    (net (code "40") (name "Net-(IC4-P3)") (class "Default")
      (node (ref "IC4") (pin "14") (pinfunction "P3_14") (pintype "bidirectional"))
      (node (ref "IC7") (pin "5") (pinfunction "I5_5") (pintype "input"))
    )
    (net (code "41") (name "Net-(IC4-P4)") (class "Default")
      (node (ref "IC4") (pin "16") (pinfunction "P4_16") (pintype "bidirectional"))
      (node (ref "IC7") (pin "4") (pinfunction "I4_4") (pintype "input"))
    )
    (net (code "42") (name "Net-(IC4-P5)") (class "Default")
      (node (ref "IC4") (pin "17") (pinfunction "P5_17") (pintype "bidirectional"))
      (node (ref "IC7") (pin "3") (pinfunction "I3_3") (pintype "input"))
    )
    (net (code "43") (name "Net-(IC4-P6)") (class "Default")
      (node (ref "IC4") (pin "19") (pinfunction "P6_19") (pintype "bidirectional"))
      (node (ref "IC7") (pin "2") (pinfunction "I2_2") (pintype "input"))
    )
    (net (code "44") (name "Net-(IC4-P7)") (class "Default")
      (node (ref "IC4") (pin "20") (pinfunction "P7_20") (pintype "bidirectional"))
      (node (ref "IC7") (pin "1") (pinfunction "I1_1") (pintype "input"))
    )
    (net (code "45") (name "Net-(IC5-AOUT)") (class "Default")
      (node (ref "IC5") (pin "15") (pinfunction "AOUT_15") (pintype "output"))
      (node (ref "TP1") (pin "TP") (pinfunction "TP_TP") (pintype "input"))
    )
    (net (code "46") (name "Net-(IC6-O1)") (class "Default")
      (node (ref "IC6") (pin "18") (pinfunction "O1_18") (pintype "open_collector"))
      (node (ref "SV1") (pin "15") (pinfunction "15_15") (pintype "passive"))
    )
    (net (code "47") (name "Net-(IC6-O2)") (class "Default")
      (node (ref "IC6") (pin "17") (pinfunction "O2_17") (pintype "open_collector"))
      (node (ref "SV1") (pin "16") (pinfunction "16_16") (pintype "passive"))
    )
    (net (code "48") (name "Net-(IC6-O3)") (class "Default")
      (node (ref "IC6") (pin "16") (pinfunction "O3_16") (pintype "open_collector"))
      (node (ref "SV1") (pin "17") (pinfunction "17_17") (pintype "passive"))
    )
    (net (code "49") (name "Net-(IC6-O4)") (class "Default")
      (node (ref "IC6") (pin "15") (pinfunction "O4_15") (pintype "open_collector"))
      (node (ref "SV1") (pin "18") (pinfunction "18_18") (pintype "passive"))
    )
    (net (code "50") (name "Net-(IC6-O5)") (class "Default")
      (node (ref "IC6") (pin "14") (pinfunction "O5_14") (pintype "open_collector"))
      (node (ref "SV1") (pin "19") (pinfunction "19_19") (pintype "passive"))
    )
    (net (code "51") (name "Net-(IC6-O6)") (class "Default")
      (node (ref "IC6") (pin "13") (pinfunction "O6_13") (pintype "open_collector"))
      (node (ref "SV1") (pin "20") (pinfunction "20_20") (pintype "passive"))
    )
    (net (code "52") (name "Net-(IC6-O7)") (class "Default")
      (node (ref "IC6") (pin "12") (pinfunction "O7_12") (pintype "open_collector"))
      (node (ref "SV1") (pin "21") (pinfunction "21_21") (pintype "passive"))
    )
    (net (code "53") (name "Net-(IC6-O8)") (class "Default")
      (node (ref "IC6") (pin "11") (pinfunction "O8_11") (pintype "open_collector"))
      (node (ref "SV1") (pin "22") (pinfunction "22_22") (pintype "passive"))
    )
    (net (code "54") (name "Net-(IC7-O1)") (class "Default")
      (node (ref "IC7") (pin "18") (pinfunction "O1_18") (pintype "open_collector"))
      (node (ref "SV1") (pin "7") (pinfunction "7_7") (pintype "passive"))
    )
    (net (code "55") (name "Net-(IC7-O2)") (class "Default")
      (node (ref "IC7") (pin "17") (pinfunction "O2_17") (pintype "open_collector"))
      (node (ref "SV1") (pin "8") (pinfunction "8_8") (pintype "passive"))
    )
    (net (code "56") (name "Net-(IC7-O3)") (class "Default")
      (node (ref "IC7") (pin "16") (pinfunction "O3_16") (pintype "open_collector"))
      (node (ref "SV1") (pin "9") (pinfunction "9_9") (pintype "passive"))
    )
    (net (code "57") (name "Net-(IC7-O4)") (class "Default")
      (node (ref "IC7") (pin "15") (pinfunction "O4_15") (pintype "open_collector"))
      (node (ref "SV1") (pin "10") (pinfunction "10_10") (pintype "passive"))
    )
    (net (code "58") (name "Net-(IC7-O5)") (class "Default")
      (node (ref "IC7") (pin "14") (pinfunction "O5_14") (pintype "open_collector"))
      (node (ref "SV1") (pin "11") (pinfunction "11_11") (pintype "passive"))
    )
    (net (code "59") (name "Net-(IC7-O6)") (class "Default")
      (node (ref "IC7") (pin "13") (pinfunction "O6_13") (pintype "open_collector"))
      (node (ref "SV1") (pin "12") (pinfunction "12_12") (pintype "passive"))
    )
    (net (code "60") (name "Net-(IC7-O7)") (class "Default")
      (node (ref "IC7") (pin "12") (pinfunction "O7_12") (pintype "open_collector"))
      (node (ref "SV1") (pin "13") (pinfunction "13_13") (pintype "passive"))
    )
    (net (code "61") (name "Net-(IC7-O8)") (class "Default")
      (node (ref "IC7") (pin "11") (pinfunction "O8_11") (pintype "open_collector"))
      (node (ref "SV1") (pin "14") (pinfunction "14_14") (pintype "passive"))
    )
    (net (code "62") (name "Net-(IC8-OSCI)") (class "Default")
      (node (ref "IC8") (pin "1") (pinfunction "OSCI_1") (pintype "bidirectional"))
      (node (ref "Q2") (pin "2") (pinfunction "2_2") (pintype "passive"))
    )
    (net (code "63") (name "Net-(IC8-OSCO)") (class "Default")
      (node (ref "IC8") (pin "2") (pinfunction "OSCO_2") (pintype "bidirectional"))
      (node (ref "Q2") (pin "1") (pinfunction "1_1") (pintype "passive"))
    )
    (net (code "64") (name "Net-(IC8-VDD)") (class "Default")
      (node (ref "C10") (pin "1") (pinfunction "1_1") (pintype "passive"))
      (node (ref "D10") (pin "C") (pinfunction "C_C") (pintype "passive"))
      (node (ref "D11") (pin "C") (pinfunction "C_C") (pintype "passive"))
      (node (ref "IC8") (pin "8") (pinfunction "VDD_8") (pintype "bidirectional"))
      (node (ref "R6") (pin "2") (pinfunction "2_2") (pintype "passive"))
    )
    (net (code "65") (name "Net-(LED1-PadA)") (class "Default")
      (node (ref "LED1") (pin "A") (pinfunction "A_A") (pintype "passive"))
      (node (ref "R3") (pin "1") (pinfunction "1_1") (pintype "passive"))
    )
    (net (code "66") (name "Net-(LED2-PadA)") (class "Default")
      (node (ref "LED2") (pin "A") (pinfunction "A_A") (pintype "passive"))
      (node (ref "R2") (pin "1") (pinfunction "1_1") (pintype "passive"))
    )
    (net (code "67") (name "Net-(LED3-PadA)") (class "Default")
      (node (ref "LED3") (pin "A") (pinfunction "A_A") (pintype "passive"))
      (node (ref "R1") (pin "1") (pinfunction "1_1") (pintype "passive"))
    )
    (net (code "68") (name "Net-(RN2A-2)") (class "Default")
      (node (ref "RN2") (pin "8") (pinfunction "2_8") (pintype "passive"))
      (node (ref "SV1") (pin "40") (pinfunction "40_40") (pintype "passive"))
    )
    (net (code "69") (name "Net-(RN2B-2)") (class "Default")
      (node (ref "RN2") (pin "7") (pinfunction "2_7") (pintype "passive"))
      (node (ref "SV1") (pin "39") (pinfunction "39_39") (pintype "passive"))
    )
    (net (code "70") (name "Net-(RN2C-2)") (class "Default")
      (node (ref "RN2") (pin "6") (pinfunction "2_6") (pintype "passive"))
      (node (ref "SV1") (pin "38") (pinfunction "38_38") (pintype "passive"))
    )
    (net (code "71") (name "Net-(RN2D-2)") (class "Default")
      (node (ref "RN2") (pin "5") (pinfunction "2_5") (pintype "passive"))
      (node (ref "SV1") (pin "37") (pinfunction "37_37") (pintype "passive"))
    )
    (net (code "72") (name "Net-(RN4A-2)") (class "Default")
      (node (ref "RN4") (pin "8") (pinfunction "2_8") (pintype "passive"))
      (node (ref "SV1") (pin "36") (pinfunction "36_36") (pintype "passive"))
    )
    (net (code "73") (name "Net-(RN4B-2)") (class "Default")
      (node (ref "RN4") (pin "7") (pinfunction "2_7") (pintype "passive"))
      (node (ref "SV1") (pin "35") (pinfunction "35_35") (pintype "passive"))
    )
    (net (code "74") (name "Net-(RN4C-2)") (class "Default")
      (node (ref "RN4") (pin "6") (pinfunction "2_6") (pintype "passive"))
      (node (ref "SV1") (pin "34") (pinfunction "34_34") (pintype "passive"))
    )
    (net (code "75") (name "Net-(RN4D-2)") (class "Default")
      (node (ref "RN4") (pin "5") (pinfunction "2_5") (pintype "passive"))
      (node (ref "SV1") (pin "33") (pinfunction "33_33") (pintype "passive"))
    )
    (net (code "76") (name "Net-(RN6A-2)") (class "Default")
      (node (ref "RN6") (pin "8") (pinfunction "2_8") (pintype "passive"))
      (node (ref "SV1") (pin "32") (pinfunction "32_32") (pintype "passive"))
    )
    (net (code "77") (name "Net-(RN6B-2)") (class "Default")
      (node (ref "RN6") (pin "7") (pinfunction "2_7") (pintype "passive"))
      (node (ref "SV1") (pin "31") (pinfunction "31_31") (pintype "passive"))
    )
    (net (code "78") (name "Net-(RN6C-2)") (class "Default")
      (node (ref "RN6") (pin "6") (pinfunction "2_6") (pintype "passive"))
      (node (ref "SV1") (pin "30") (pinfunction "30_30") (pintype "passive"))
    )
    (net (code "79") (name "Net-(RN6D-2)") (class "Default")
      (node (ref "RN6") (pin "5") (pinfunction "2_5") (pintype "passive"))
      (node (ref "SV1") (pin "29") (pinfunction "29_29") (pintype "passive"))
    )
    (net (code "80") (name "Net-(RN8A-2)") (class "Default")
      (node (ref "RN8") (pin "8") (pinfunction "2_8") (pintype "passive"))
      (node (ref "SV1") (pin "28") (pinfunction "28_28") (pintype "passive"))
    )
    (net (code "81") (name "Net-(RN8B-2)") (class "Default")
      (node (ref "RN8") (pin "7") (pinfunction "2_7") (pintype "passive"))
      (node (ref "SV1") (pin "27") (pinfunction "27_27") (pintype "passive"))
    )
    (net (code "82") (name "Net-(RN8C-2)") (class "Default")
      (node (ref "RN8") (pin "6") (pinfunction "2_6") (pintype "passive"))
      (node (ref "SV1") (pin "26") (pinfunction "26_26") (pintype "passive"))
    )
    (net (code "83") (name "Net-(RN8D-2)") (class "Default")
      (node (ref "RN8") (pin "5") (pinfunction "2_5") (pintype "passive"))
      (node (ref "SV1") (pin "25") (pinfunction "25_25") (pintype "passive"))
    )
    (net (code "84") (name "Net-(RN10A-2)") (class "Default")
      (node (ref "RN10") (pin "8") (pinfunction "2_8") (pintype "passive"))
      (node (ref "SV1") (pin "4") (pinfunction "4_4") (pintype "passive"))
    )
    (net (code "85") (name "Net-(RN10B-2)") (class "Default")
      (node (ref "RN10") (pin "7") (pinfunction "2_7") (pintype "passive"))
      (node (ref "SV1") (pin "2") (pinfunction "2_2") (pintype "passive"))
    )
    (net (code "86") (name "Net-(RN10C-2)") (class "Default")
      (node (ref "RN10") (pin "6") (pinfunction "2_6") (pintype "passive"))
      (node (ref "SV1") (pin "1") (pinfunction "1_1") (pintype "passive"))
    )
    (net (code "87") (name "Net-(RN10D-2)") (class "Default")
      (node (ref "RN10") (pin "5") (pinfunction "2_5") (pintype "passive"))
      (node (ref "SV1") (pin "3") (pinfunction "3_3") (pintype "passive"))
    )
    (net (code "88") (name "Net-(U$1-18-GPIO5)") (class "Default")
      (node (ref "SJ2") (pin "1") (pinfunction "1_1") (pintype "passive"))
      (node (ref "U$1") (pin "18") (pinfunction "18-GPIO5_18") (pintype "bidirectional"))
    )
    (net (code "89") (name "Net-(U$1-19-SPI-MOSI)") (class "Default")
      (node (ref "U$1") (pin "19") (pinfunction "19-SPI-MOSI_19") (pintype "bidirectional"))
      (node (ref "U2") (pin "14") (pinfunction "SI_14") (pintype "input"))
    )
    (net (code "90") (name "Net-(U$1-21-SPI-MISO)") (class "Default")
      (node (ref "U$1") (pin "21") (pinfunction "21-SPI-MISO_21") (pintype "bidirectional"))
      (node (ref "U2") (pin "15") (pinfunction "SO_15") (pintype "output"))
    )
    (net (code "91") (name "Net-(U$1-22-GPIO6)") (class "Default")
      (node (ref "SJ2") (pin "3") (pinfunction "3_3") (pintype "passive"))
      (node (ref "U$1") (pin "22") (pinfunction "22-GPIO6_22") (pintype "bidirectional"))
    )
    (net (code "92") (name "Net-(U$1-23-SPI-SCLK)") (class "Default")
      (node (ref "U$1") (pin "23") (pinfunction "23-SPI-SCLK_23") (pintype "bidirectional"))
      (node (ref "U2") (pin "13") (pinfunction "SCK_13") (pintype "input"))
    )
    (net (code "93") (name "Net-(U$1-24-SPI-CE0-N)") (class "Default")
      (node (ref "SJ1") (pin "1") (pinfunction "1_1") (pintype "passive"))
      (node (ref "U$1") (pin "24") (pinfunction "24-SPI-CE0-N_24") (pintype "bidirectional"))
    )
    (net (code "94") (name "Net-(U$1-26-SPI-CE1-N)") (class "Default")
      (node (ref "SJ1") (pin "3") (pinfunction "3_3") (pintype "passive"))
      (node (ref "U$1") (pin "26") (pinfunction "26-SPI-CE1-N_26") (pintype "bidirectional"))
    )
    (net (code "95") (name "Net-(U$2-BOOT)") (class "Default")
      (node (ref "C14") (pin "1") (pinfunction "1_1") (pintype "passive"))
      (node (ref "U$2") (pin "1") (pinfunction "BOOT_1") (pintype "bidirectional"))
    )
    (net (code "96") (name "Net-(U$2-COMP)") (class "Default")
      (node (ref "C16") (pin "2") (pinfunction "2_2") (pintype "passive"))
      (node (ref "R13") (pin "1") (pinfunction "1_1") (pintype "passive"))
      (node (ref "U$2") (pin "6") (pinfunction "COMP_6") (pintype "bidirectional"))
    )
    (net (code "97") (name "Net-(U$2-EN)") (class "Default")
      (node (ref "R15") (pin "1") (pinfunction "1_1") (pintype "passive"))
      (node (ref "R16") (pin "2") (pinfunction "2_2") (pintype "passive"))
      (node (ref "U$2") (pin "3") (pinfunction "EN_3") (pintype "bidirectional"))
    )
    (net (code "98") (name "Net-(U$2-FB)") (class "Default")
      (node (ref "R11") (pin "2") (pinfunction "2_2") (pintype "passive"))
      (node (ref "R12") (pin "1") (pinfunction "1_1") (pintype "passive"))
      (node (ref "U$2") (pin "5") (pinfunction "FB_5") (pintype "bidirectional"))
    )
    (net (code "99") (name "Net-(U$2-RT{slash}CLK)") (class "Default")
      (node (ref "R14") (pin "1") (pinfunction "1_1") (pintype "passive"))
      (node (ref "U$2") (pin "4") (pinfunction "RT/CLK_4") (pintype "bidirectional"))
    )
    (net (code "100") (name "Net-(U$2-SW)") (class "Default")
      (node (ref "C14") (pin "2") (pinfunction "2_2") (pintype "passive"))
      (node (ref "D14") (pin "C") (pinfunction "C_C") (pintype "passive"))
      (node (ref "L1") (pin "1") (pinfunction "1_1") (pintype "passive"))
      (node (ref "U$2") (pin "8") (pinfunction "SW_8") (pintype "bidirectional"))
    )
    (net (code "101") (name "Net-(U1A-CANH)") (class "Default")
      (node (ref "U1") (pin "7") (pinfunction "CANH_7") (pintype "bidirectional"))
      (node (ref "X1") (pin "4") (pinfunction "1_4") (pintype "passive"))
    )
    (net (code "102") (name "Net-(U1A-CANL)") (class "Default")
      (node (ref "U1") (pin "6") (pinfunction "CANL_6") (pintype "bidirectional"))
      (node (ref "X1") (pin "2") (pinfunction "1_2") (pintype "passive"))
    )
    (net (code "103") (name "Net-(U1A-RXD)") (class "Default")
      (node (ref "R2") (pin "2") (pinfunction "2_2") (pintype "passive"))
      (node (ref "R4") (pin "1") (pinfunction "1_1") (pintype "passive"))
      (node (ref "U1") (pin "4") (pinfunction "RXD_4") (pintype "output"))
    )
    (net (code "104") (name "Net-(U1A-TXD)") (class "Default")
      (node (ref "R1") (pin "2") (pinfunction "2_2") (pintype "passive"))
      (node (ref "U1") (pin "1") (pinfunction "TXD_1") (pintype "input"))
      (node (ref "U2") (pin "1") (pinfunction "TXCAN_1") (pintype "output"))
    )
    (net (code "105") (name "Net-(U2A-CS)") (class "Default")
      (node (ref "R7") (pin "2") (pinfunction "2_2") (pintype "passive"))
      (node (ref "SJ1") (pin "2") (pinfunction "2_2") (pintype "passive"))
      (node (ref "U2") (pin "16") (pinfunction "CS_16") (pintype "input"))
    )
    (net (code "106") (name "Net-(U2A-INT)") (class "Default")
      (node (ref "SJ2") (pin "2") (pinfunction "2_2") (pintype "passive"))
      (node (ref "U2") (pin "12") (pinfunction "INT_12") (pintype "output"))
    )
    (net (code "107") (name "Net-(U2A-OSC1)") (class "Default")
      (node (ref "C2") (pin "1") (pinfunction "1_1") (pintype "passive"))
      (node (ref "Q1") (pin "1") (pinfunction "1_1") (pintype "passive"))
      (node (ref "U2") (pin "8") (pinfunction "OSC1_8") (pintype "input"))
    )
    (net (code "108") (name "Net-(U2A-OSC2)") (class "Default")
      (node (ref "C3") (pin "1") (pinfunction "1_1") (pintype "passive"))
      (node (ref "Q1") (pin "2") (pinfunction "2_2") (pintype "passive"))
      (node (ref "U2") (pin "7") (pinfunction "OSC2_7") (pintype "output"))
    )
    (net (code "109") (name "Net-(U2A-RESET)") (class "Default")
      (node (ref "R10") (pin "1") (pinfunction "1_1") (pintype "passive"))
      (node (ref "U2") (pin "17") (pinfunction "RESET_17") (pintype "input"))
    )
    (net (code "110") (name "Net-(U2A-RXCAN)") (class "Default")
      (node (ref "R4") (pin "2") (pinfunction "2_2") (pintype "passive"))
      (node (ref "R5") (pin "1") (pinfunction "1_1") (pintype "passive"))
      (node (ref "U2") (pin "2") (pinfunction "RXCAN_2") (pintype "input"))
    )
    (net (code "111") (name "Net-(X1E-1)") (class "Default")
      (node (ref "D1") (pin "A") (pinfunction "A_A") (pintype "passive"))
      (node (ref "X1") (pin "5") (pinfunction "1_5") (pintype "passive"))
    )
    (net (code "112") (name "VDD") (class "Default")
      (node (ref "C17") (pin "2") (pinfunction "2_2") (pintype "passive"))
      (node (ref "C4") (pin "1") (pinfunction "1_1") (pintype "passive"))
      (node (ref "L1") (pin "2") (pinfunction "2_2") (pintype "passive"))
      (node (ref "R11") (pin "1") (pinfunction "1_1") (pintype "passive"))
      (node (ref "R3") (pin "2") (pinfunction "2_2") (pintype "passive"))
      (node (ref "TP2") (pin "TP") (pinfunction "TP_TP") (pintype "input"))
      (node (ref "U$1") (pin "2") (pinfunction "2-+5V_2") (pintype "bidirectional"))
    )
    (net (code "113") (name "VSS") (class "Default")
      (node (ref "C1") (pin "2") (pinfunction "2_2") (pintype "passive"))
      (node (ref "C10") (pin "2") (pinfunction "2_2") (pintype "passive"))
      (node (ref "C12") (pin "-") (pinfunction "-_-") (pintype "passive"))
      (node (ref "C13") (pin "-") (pinfunction "-_-") (pintype "passive"))
      (node (ref "C15") (pin "1") (pinfunction "1_1") (pintype "passive"))
      (node (ref "C16") (pin "1") (pinfunction "1_1") (pintype "passive"))
      (node (ref "C17") (pin "1") (pinfunction "1_1") (pintype "passive"))
      (node (ref "C18") (pin "1") (pinfunction "1_1") (pintype "passive"))
      (node (ref "C2") (pin "2") (pinfunction "2_2") (pintype "passive"))
      (node (ref "C3") (pin "2") (pinfunction "2_2") (pintype "passive"))
      (node (ref "C4") (pin "2") (pinfunction "2_2") (pintype "passive"))
      (node (ref "C5") (pin "2") (pinfunction "2_2") (pintype "passive"))
      (node (ref "C6") (pin "2") (pinfunction "2_2") (pintype "passive"))
      (node (ref "C7") (pin "2") (pinfunction "2_2") (pintype "passive"))
      (node (ref "C8") (pin "2") (pinfunction "2_2") (pintype "passive"))
      (node (ref "C9") (pin "2") (pinfunction "2_2") (pintype "passive"))
      (node (ref "D12") (pin "1") (pinfunction "A_1") (pintype "passive"))
      (node (ref "D13") (pin "1") (pinfunction "A_1") (pintype "passive"))
      (node (ref "D14") (pin "A") (pinfunction "A_A") (pintype "passive"))
      (node (ref "D2") (pin "1") (pinfunction "A_1") (pintype "passive"))
      (node (ref "D3") (pin "1") (pinfunction "A_1") (pintype "passive"))
      (node (ref "D4") (pin "1") (pinfunction "A_1") (pintype "passive"))
      (node (ref "D5") (pin "1") (pinfunction "A_1") (pintype "passive"))
      (node (ref "D6") (pin "1") (pinfunction "A_1") (pintype "passive"))
      (node (ref "D7") (pin "1") (pinfunction "A_1") (pintype "passive"))
      (node (ref "D8") (pin "1") (pinfunction "A_1") (pintype "passive"))
      (node (ref "D9") (pin "1") (pinfunction "A_1") (pintype "passive"))
      (node (ref "G1") (pin "-") (pinfunction "-_-") (pintype "passive"))
      (node (ref "IC1") (pin "15") (pinfunction "VSS_15") (pintype "power_in"))
      (node (ref "IC1") (pin "7") (pinfunction "A1_7") (pintype "input"))
      (node (ref "IC2") (pin "15") (pinfunction "VSS_15") (pintype "power_in"))
      (node (ref "IC2") (pin "6") (pinfunction "A0_6") (pintype "input"))
      (node (ref "IC2") (pin "7") (pinfunction "A1_7") (pintype "input"))
      (node (ref "IC3") (pin "15") (pinfunction "VSS_15") (pintype "power_in"))
      (node (ref "IC3") (pin "6") (pinfunction "A0_6") (pintype "input"))
      (node (ref "IC4") (pin "15") (pinfunction "VSS_15") (pintype "power_in"))
      (node (ref "IC5") (pin "12") (pinfunction "EXT_12") (pintype "input"))
      (node (ref "IC5") (pin "13") (pinfunction "AGND_13") (pintype "power_in"))
      (node (ref "IC5") (pin "5") (pinfunction "A0_5") (pintype "input"))
      (node (ref "IC5") (pin "6") (pinfunction "A1_6") (pintype "input"))
      (node (ref "IC5") (pin "8") (pinfunction "VSS_8") (pintype "power_in"))
      (node (ref "IC6") (pin "9") (pinfunction "GND_9") (pintype "power_in"))
      (node (ref "IC7") (pin "9") (pinfunction "GND_9") (pintype "power_in"))
      (node (ref "IC8") (pin "4") (pinfunction "VSS_4") (pintype "bidirectional"))
      (node (ref "LED1") (pin "C") (pinfunction "C_C") (pintype "passive"))
      (node (ref "LED2") (pin "C") (pinfunction "C_C") (pintype "passive"))
      (node (ref "LED3") (pin "C") (pinfunction "C_C") (pintype "passive"))
      (node (ref "R12") (pin "2") (pinfunction "2_2") (pintype "passive"))
      (node (ref "R14") (pin "2") (pinfunction "2_2") (pintype "passive"))
      (node (ref "R15") (pin "2") (pinfunction "2_2") (pintype "passive"))
      (node (ref "R5") (pin "2") (pinfunction "2_2") (pintype "passive"))
      (node (ref "RN1") (pin "1") (pinfunction "1_1") (pintype "passive"))
      (node (ref "RN1") (pin "2") (pinfunction "1_2") (pintype "passive"))
      (node (ref "RN1") (pin "3") (pinfunction "1_3") (pintype "passive"))
      (node (ref "RN1") (pin "4") (pinfunction "1_4") (pintype "passive"))
      (node (ref "RN3") (pin "1") (pinfunction "1_1") (pintype "passive"))
      (node (ref "RN3") (pin "2") (pinfunction "1_2") (pintype "passive"))
      (node (ref "RN3") (pin "3") (pinfunction "1_3") (pintype "passive"))
      (node (ref "RN3") (pin "4") (pinfunction "1_4") (pintype "passive"))
      (node (ref "RN5") (pin "1") (pinfunction "1_1") (pintype "passive"))
      (node (ref "RN5") (pin "2") (pinfunction "1_2") (pintype "passive"))
      (node (ref "RN5") (pin "3") (pinfunction "1_3") (pintype "passive"))
      (node (ref "RN5") (pin "4") (pinfunction "1_4") (pintype "passive"))
      (node (ref "RN7") (pin "1") (pinfunction "1_1") (pintype "passive"))
      (node (ref "RN7") (pin "2") (pinfunction "1_2") (pintype "passive"))
      (node (ref "RN7") (pin "3") (pinfunction "1_3") (pintype "passive"))
      (node (ref "RN7") (pin "4") (pinfunction "1_4") (pintype "passive"))
      (node (ref "RN9") (pin "1") (pinfunction "1_1") (pintype "passive"))
      (node (ref "RN9") (pin "2") (pinfunction "1_2") (pintype "passive"))
      (node (ref "RN9") (pin "3") (pinfunction "1_3") (pintype "passive"))
      (node (ref "RN9") (pin "4") (pinfunction "1_4") (pintype "passive"))
      (node (ref "SJ3") (pin "3") (pinfunction "3_3") (pintype "passive"))
      (node (ref "SV1") (pin "5") (pinfunction "5_5") (pintype "passive"))
      (node (ref "SV1") (pin "6") (pinfunction "6_6") (pintype "passive"))
      (node (ref "TP4") (pin "TP") (pinfunction "TP_TP") (pintype "input"))
      (node (ref "U$1") (pin "6") (pinfunction "6-GND_6") (pintype "bidirectional"))
      (node (ref "U$2") (pin "7") (pinfunction "GND_7") (pintype "bidirectional"))
      (node (ref "U1") (pin "5") (pinfunction "VREF_5") (pintype "power_in"))
      (node (ref "U1") (pin "8") (pinfunction "RS_8") (pintype "input"))
      (node (ref "U2") (pin "9") (pinfunction "VSS_9") (pintype "power_in"))
      (node (ref "X1") (pin "1") (pinfunction "1_1") (pintype "passive"))
    )
    (net (code "114") (name "unconnected-(G1-+-Pad+@1)") (class "Default")
      (node (ref "G1") (pin "+@1") (pinfunction "+_+@1") (pintype "passive"))
    )
    (net (code "115") (name "unconnected-(IC1-~{INT}-Pad1)") (class "Default")
      (node (ref "IC1") (pin "1") (pinfunction "~{INT}_1") (pintype "output"))
    )
    (net (code "116") (name "unconnected-(IC2-~{INT}-Pad1)") (class "Default")
      (node (ref "IC2") (pin "1") (pinfunction "~{INT}_1") (pintype "output"))
    )
    (net (code "117") (name "unconnected-(IC3-~{INT}-Pad1)") (class "Default")
      (node (ref "IC3") (pin "1") (pinfunction "~{INT}_1") (pintype "output"))
    )
    (net (code "118") (name "unconnected-(IC4-~{INT}-Pad1)") (class "Default")
      (node (ref "IC4") (pin "1") (pinfunction "~{INT}_1") (pintype "output"))
    )
    (net (code "119") (name "unconnected-(IC5-OSC-Pad11)") (class "Default")
      (node (ref "IC5") (pin "11") (pinfunction "OSC_11") (pintype "input"))
    )
    (net (code "120") (name "unconnected-(IC8-CLKOUT-Pad7)") (class "Default")
      (node (ref "IC8") (pin "7") (pinfunction "CLKOUT_7") (pintype "bidirectional"))
    )
    (net (code "121") (name "unconnected-(IC8-INT#-Pad3)") (class "Default")
      (node (ref "IC8") (pin "3") (pinfunction "INT#_3") (pintype "bidirectional"))
    )
    (net (code "122") (name "unconnected-(U$1-4-DNC-Pad4)") (class "Default")
      (node (ref "U$1") (pin "4") (pinfunction "4-DNC_4") (pintype "bidirectional"))
    )
    (net (code "123") (name "unconnected-(U$1-7-GPIO7-Pad7)") (class "Default")
      (node (ref "U$1") (pin "7") (pinfunction "7-GPIO7_7") (pintype "bidirectional"))
    )
    (net (code "124") (name "unconnected-(U$1-8-TX-Pad8)") (class "Default")
      (node (ref "U$1") (pin "8") (pinfunction "8-TX_8") (pintype "bidirectional"))
    )
    (net (code "125") (name "unconnected-(U$1-9-DNC-Pad9)") (class "Default")
      (node (ref "U$1") (pin "9") (pinfunction "9-DNC_9") (pintype "bidirectional"))
    )
    (net (code "126") (name "unconnected-(U$1-10-RX-Pad10)") (class "Default")
      (node (ref "U$1") (pin "10") (pinfunction "10-RX_10") (pintype "bidirectional"))
    )
    (net (code "127") (name "unconnected-(U$1-11-GPIO0-Pad11)") (class "Default")
      (node (ref "U$1") (pin "11") (pinfunction "11-GPIO0_11") (pintype "bidirectional"))
    )
    (net (code "128") (name "unconnected-(U$1-12-GPIO1-Pad12)") (class "Default")
      (node (ref "U$1") (pin "12") (pinfunction "12-GPIO1_12") (pintype "bidirectional"))
    )
    (net (code "129") (name "unconnected-(U$1-13-GPIO2-Pad13)") (class "Default")
      (node (ref "U$1") (pin "13") (pinfunction "13-GPIO2_13") (pintype "bidirectional"))
    )
    (net (code "130") (name "unconnected-(U$1-14-DNC-Pad14)") (class "Default")
      (node (ref "U$1") (pin "14") (pinfunction "14-DNC_14") (pintype "bidirectional"))
    )
    (net (code "131") (name "unconnected-(U$1-15-GPIO3-Pad15)") (class "Default")
      (node (ref "U$1") (pin "15") (pinfunction "15-GPIO3_15") (pintype "bidirectional"))
    )
    (net (code "132") (name "unconnected-(U$1-16-GPIO4-Pad16)") (class "Default")
      (node (ref "U$1") (pin "16") (pinfunction "16-GPIO4_16") (pintype "bidirectional"))
    )
    (net (code "133") (name "unconnected-(U$1-17-DNC-Pad17)") (class "Default")
      (node (ref "U$1") (pin "17") (pinfunction "17-DNC_17") (pintype "bidirectional"))
    )
    (net (code "134") (name "unconnected-(U$1-20-DNC-Pad20)") (class "Default")
      (node (ref "U$1") (pin "20") (pinfunction "20-DNC_20") (pintype "bidirectional"))
    )
    (net (code "135") (name "unconnected-(U$1-25-DNC-Pad25)") (class "Default")
      (node (ref "U$1") (pin "25") (pinfunction "25-DNC_25") (pintype "bidirectional"))
    )
    (net (code "136") (name "unconnected-(U2A-CLKOUT-Pad3)") (class "Default")
      (node (ref "U2") (pin "3") (pinfunction "CLKOUT_3") (pintype "output"))
    )
    (net (code "137") (name "unconnected-(U2A-RX0BF-Pad11)") (class "Default")
      (node (ref "U2") (pin "11") (pinfunction "RX0BF_11") (pintype "output"))
    )
    (net (code "138") (name "unconnected-(U2A-RX1BF-Pad10)") (class "Default")
      (node (ref "U2") (pin "10") (pinfunction "RX1BF_10") (pintype "output"))
    )
    (net (code "139") (name "unconnected-(U2A-TX0RTS-Pad4)") (class "Default")
      (node (ref "U2") (pin "4") (pinfunction "TX0RTS_4") (pintype "input"))
    )
    (net (code "140") (name "unconnected-(U2A-TX1RTS-Pad5)") (class "Default")
      (node (ref "U2") (pin "5") (pinfunction "TX1RTS_5") (pintype "input"))
    )
    (net (code "141") (name "unconnected-(U2A-TX2RTS-Pad6)") (class "Default")
      (node (ref "U2") (pin "6") (pinfunction "TX2RTS_6") (pintype "input"))
    )
    (net (code "142") (name "unconnected-(X1C-1-Pad3)") (class "Default")
      (node (ref "X1") (pin "3") (pinfunction "1_3") (pintype "passive"))
    )
  )
)
